# ssr-breakout2.net
KiCad netlist of a schematic drawn in EAGLE
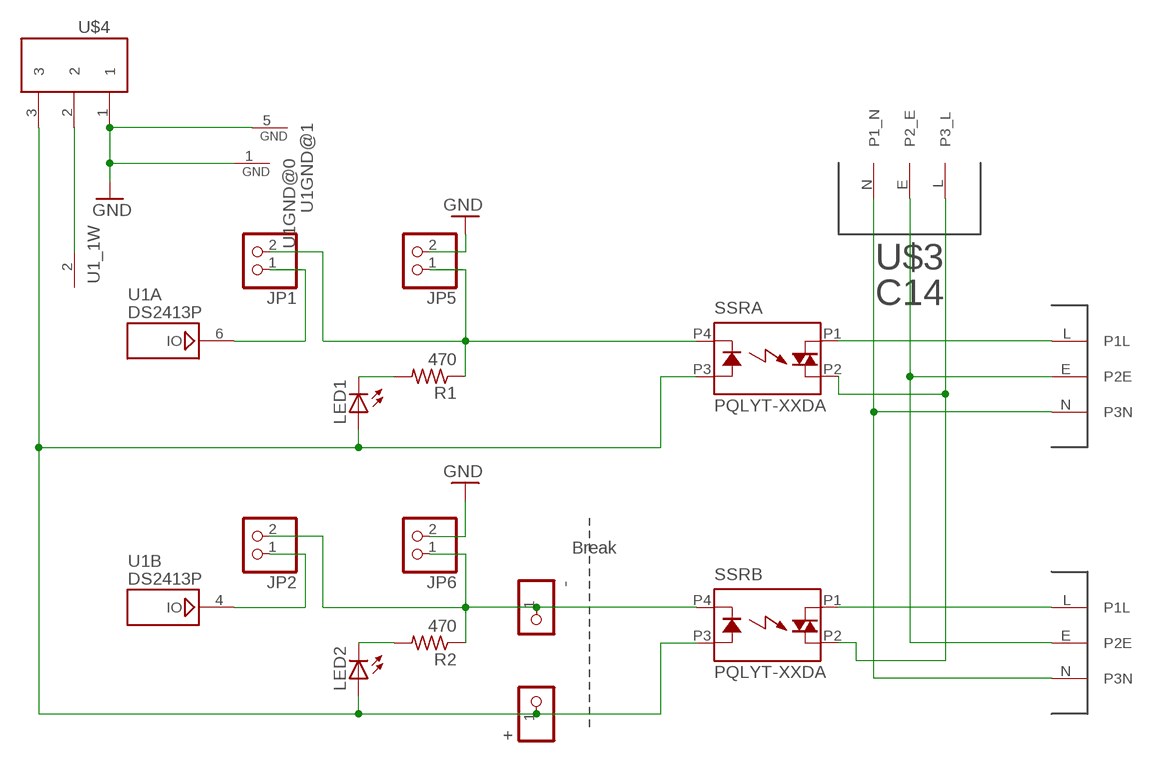
[diagram p0: schematic, sheet 1]

(export (version "E")
  (design (tool "Eeschema 10.0.6"))
  (components
    (comp (ref "+")
      (value "PINHD-1X1CB")
      (footprint "eagle-import:1X01-CLEANBIG")
      (libsource (lib "eagle-import") (part "PINHD-1X1CB"))
    )
    (comp (ref "-")
      (value "PINHD-1X1CB")
      (footprint "eagle-import:1X01-CLEANBIG")
      (libsource (lib "eagle-import") (part "PINHD-1X1CB"))
    )
    (comp (ref "JP1")
      (value "PINHD-1X2")
      (footprint "eagle-import:1X02")
      (libsource (lib "eagle-import") (part "PINHD-1X2"))
    )
    (comp (ref "JP2")
      (value "PINHD-1X2")
      (footprint "eagle-import:1X02")
      (libsource (lib "eagle-import") (part "PINHD-1X2"))
    )
    (comp (ref "JP5")
      (value "PINHD-1X2")
      (footprint "eagle-import:1X02")
      (libsource (lib "eagle-import") (part "PINHD-1X2"))
    )
    (comp (ref "JP6")
      (value "PINHD-1X2")
      (footprint "eagle-import:1X02")
      (libsource (lib "eagle-import") (part "PINHD-1X2"))
    )
    (comp (ref "LED1")
      (value "LEDCHIPLED_0805")
      (footprint "eagle-import:CHIPLED_0805")
      (libsource (lib "eagle-import") (part "LEDCHIPLED_0805"))
    )
    (comp (ref "LED2")
      (value "LEDCHIPLED_0805")
      (footprint "eagle-import:CHIPLED_0805")
      (libsource (lib "eagle-import") (part "LEDCHIPLED_0805"))
    )
    (comp (ref "R1")
      (value "470")
      (footprint "eagle-import:R0805")
      (libsource (lib "eagle-import") (part "R-US_R0805"))
    )
    (comp (ref "R2")
      (value "470")
      (footprint "eagle-import:R0805")
      (libsource (lib "eagle-import") (part "R-US_R0805"))
    )
    (comp (ref "SSRA")
      (value "PQLYT-XXDA")
      (footprint "eagle-import:PQLYT")
      (libsource (lib "eagle-import") (part "PQLYT-XXDA"))
    )
    (comp (ref "SSRB")
      (value "PQLYT-XXDA")
      (footprint "eagle-import:PQLYT")
      (libsource (lib "eagle-import") (part "PQLYT-XXDA"))
    )
    (comp (ref "U$3")
      (value "C14")
      (footprint "eagle-import:6ESRM-P")
      (libsource (lib "eagle-import") (part "C14"))
    )
    (comp (ref "U$4")
      (value "3.5MM3PHORIZONTAL")
      (footprint "eagle-import:3.5MM3P")
      (libsource (lib "eagle-import") (part "3.5MM3PHORIZONTAL"))
    )
    (comp (ref "U$5")
      (value "C13")
      (footprint "eagle-import:PX0695_10_PC")
      (libsource (lib "eagle-import") (part "C13"))
    )
    (comp (ref "U$6")
      (value "C13")
      (footprint "eagle-import:PX0695_10_PC")
      (libsource (lib "eagle-import") (part "C13"))
    )
    (comp (ref "U1")
      (value "DS2413P")
      (footprint "eagle-import:TSOC6")
      (libsource (lib "eagle-import") (part "DS2413P"))
    )
  )
  (nets
    (net (code "1") (name "GND") (class "Default")
      (node (ref "JP5") (pin "2") (pinfunction "2_2") (pintype "passive"))
      (node (ref "JP6") (pin "2") (pinfunction "2_2") (pintype "passive"))
      (node (ref "U$4") (pin "1") (pinfunction "1_1") (pintype "bidirectional"))
      (node (ref "U1") (pin "1") (pinfunction "GND_1") (pintype "power_in"))
      (node (ref "U1") (pin "5") (pinfunction "GND_5") (pintype "power_in"))
    )
    (net (code "2") (name "Net-(LED1-PadC)") (class "Default")
      (node (ref "LED1") (pin "C") (pinfunction "C_C") (pintype "passive"))
      (node (ref "R1") (pin "2") (pinfunction "2_2") (pintype "passive"))
    )
    (net (code "3") (name "Net-(LED2-PadC)") (class "Default")
      (node (ref "LED2") (pin "C") (pinfunction "C_C") (pintype "passive"))
      (node (ref "R2") (pin "2") (pinfunction "2_2") (pintype "passive"))
    )
    (net (code "4") (name "Net-(SSRA-A)") (class "Default")
      (node (ref "+") (pin "1") (pinfunction "1_1") (pintype "passive"))
      (node (ref "LED1") (pin "A") (pinfunction "A_A") (pintype "passive"))
      (node (ref "LED2") (pin "A") (pinfunction "A_A") (pintype "passive"))
      (node (ref "SSRA") (pin "P3") (pinfunction "A_P3") (pintype "passive"))
      (node (ref "SSRB") (pin "P3") (pinfunction "A_P3") (pintype "passive"))
      (node (ref "U$4") (pin "3") (pinfunction "3_3") (pintype "bidirectional"))
    )
    (net (code "5") (name "Net-(SSRA-DS1)") (class "Default")
      (node (ref "SSRA") (pin "P1") (pinfunction "DS1_P1") (pintype "passive"))
      (node (ref "U$5") (pin "L") (pinfunction "P1L_L") (pintype "bidirectional"))
    )
    (net (code "6") (name "Net-(SSRA-DS2)") (class "Default")
      (node (ref "SSRA") (pin "P2") (pinfunction "DS2_P2") (pintype "passive"))
      (node (ref "SSRB") (pin "P2") (pinfunction "DS2_P2") (pintype "passive"))
      (node (ref "U$3") (pin "L") (pinfunction "P3_L_L") (pintype "bidirectional"))
    )
    (net (code "7") (name "Net-(SSRA-K)") (class "Default")
      (node (ref "JP1") (pin "2") (pinfunction "2_2") (pintype "passive"))
      (node (ref "JP5") (pin "1") (pinfunction "1_1") (pintype "passive"))
      (node (ref "R1") (pin "1") (pinfunction "1_1") (pintype "passive"))
      (node (ref "SSRA") (pin "P4") (pinfunction "K_P4") (pintype "passive"))
    )
    (net (code "8") (name "Net-(SSRB-DS1)") (class "Default")
      (node (ref "SSRB") (pin "P1") (pinfunction "DS1_P1") (pintype "passive"))
      (node (ref "U$6") (pin "L") (pinfunction "P1L_L") (pintype "bidirectional"))
    )
    (net (code "9") (name "Net-(SSRB-K)") (class "Default")
      (node (ref "-") (pin "1") (pinfunction "1_1") (pintype "passive"))
      (node (ref "JP2") (pin "2") (pinfunction "2_2") (pintype "passive"))
      (node (ref "JP6") (pin "1") (pinfunction "1_1") (pintype "passive"))
      (node (ref "R2") (pin "1") (pinfunction "1_1") (pintype "passive"))
      (node (ref "SSRB") (pin "P4") (pinfunction "K_P4") (pintype "passive"))
    )
    (net (code "10") (name "Net-(U$3-P1_N)") (class "Default")
      (node (ref "U$3") (pin "N") (pinfunction "P1_N_N") (pintype "bidirectional"))
      (node (ref "U$5") (pin "N") (pinfunction "P3N_N") (pintype "bidirectional"))
      (node (ref "U$6") (pin "N") (pinfunction "P3N_N") (pintype "bidirectional"))
    )
    (net (code "11") (name "Net-(U$3-P2_E)") (class "Default")
      (node (ref "U$3") (pin "E") (pinfunction "P2_E_E") (pintype "bidirectional"))
      (node (ref "U$5") (pin "E") (pinfunction "P2E_E") (pintype "bidirectional"))
      (node (ref "U$6") (pin "E") (pinfunction "P2E_E") (pintype "bidirectional"))
    )
    (net (code "12") (name "Net-(U1A-IO)") (class "Default")
      (node (ref "JP1") (pin "1") (pinfunction "1_1") (pintype "passive"))
      (node (ref "U1") (pin "6") (pinfunction "IO_6") (pintype "open_collector"))
    )
    (net (code "13") (name "Net-(U1B-IO)") (class "Default")
      (node (ref "JP2") (pin "1") (pinfunction "1_1") (pintype "passive"))
      (node (ref "U1") (pin "4") (pinfunction "IO_4") (pintype "open_collector"))
    )
    (net (code "14") (name "Net-(U1E-1W)") (class "Default")
      (node (ref "U$4") (pin "2") (pinfunction "2_2") (pintype "bidirectional"))
      (node (ref "U1") (pin "2") (pinfunction "1W_2") (pintype "power_in"))
    )
  )
)
